# Full_set.net
KiCad netlist of a schematic drawn in EAGLE
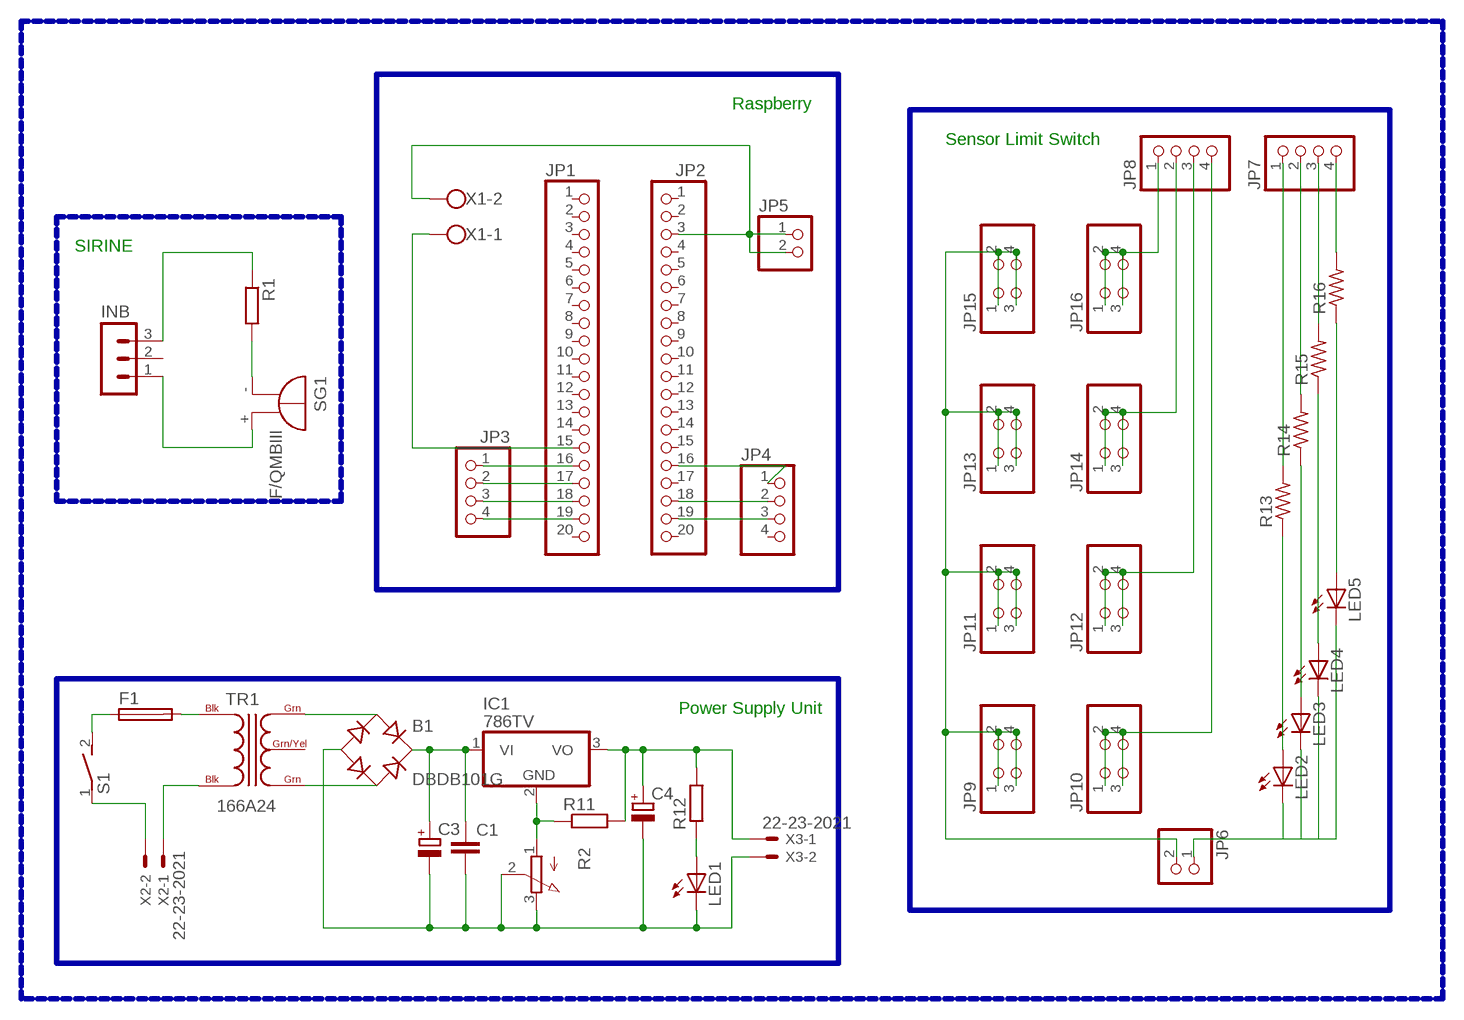
[diagram p0: schematic, sheet 1]

(export (version "E")
  (design (tool "Eeschema 10.0.6"))
  (components
    (comp (ref "B1")
      (value "DBDB101G")
      (footprint "eagle-import:DB")
      (libsource (lib "eagle-import") (part "DB?GDB101"))
    )
    (comp (ref "C1")
      (value "C-EU075-032X103")
      (footprint "eagle-import:C075-032X103")
      (libsource (lib "eagle-import") (part "C-EU075-032X103"))
    )
    (comp (ref "C3")
      (value "CPOL-EUE5-8.5")
      (footprint "eagle-import:E5-8,5")
      (libsource (lib "eagle-import") (part "CPOL-EUE5-8.5"))
    )
    (comp (ref "C4")
      (value "CPOL-EUE5-6")
      (footprint "eagle-import:E5-6")
      (libsource (lib "eagle-import") (part "CPOL-EUE5-6"))
    )
    (comp (ref "F1")
      (value "19560")
      (footprint "eagle-import:19560")
      (fields (field (name "MPN") "56000001009"))
      (libsource (lib "eagle-import") (part "19560"))
    )
    (comp (ref "IC1")
      (value "786TV")
      (footprint "eagle-import:TO220V")
      (libsource (lib "eagle-import") (part "78TV6"))
    )
    (comp (ref "INB")
      (value "MA03-1")
      (footprint "eagle-import:MA03-1")
      (libsource (lib "eagle-import") (part "MA03-1"))
    )
    (comp (ref "JP1")
      (value "PINHD-1X20")
      (footprint "eagle-import:1X20")
      (libsource (lib "eagle-import") (part "PINHD-1X20"))
    )
    (comp (ref "JP2")
      (value "PINHD-1X20")
      (footprint "eagle-import:1X20")
      (libsource (lib "eagle-import") (part "PINHD-1X20"))
    )
    (comp (ref "JP3")
      (value "PINHD-1X4")
      (footprint "eagle-import:1X04")
      (libsource (lib "eagle-import") (part "PINHD-1X4"))
    )
    (comp (ref "JP4")
      (value "PINHD-1X4")
      (footprint "eagle-import:1X04")
      (libsource (lib "eagle-import") (part "PINHD-1X4"))
    )
    (comp (ref "JP5")
      (value "PINHD-1X2")
      (footprint "eagle-import:1X02")
      (libsource (lib "eagle-import") (part "PINHD-1X2"))
    )
    (comp (ref "JP6")
      (value "PINHD-1X2")
      (footprint "eagle-import:1X02")
      (libsource (lib "eagle-import") (part "PINHD-1X2"))
    )
    (comp (ref "JP7")
      (value "PINHD-1X4")
      (footprint "eagle-import:1X04")
      (libsource (lib "eagle-import") (part "PINHD-1X4"))
    )
    (comp (ref "JP8")
      (value "PINHD-1X4")
      (footprint "eagle-import:1X04")
      (libsource (lib "eagle-import") (part "PINHD-1X4"))
    )
    (comp (ref "JP9")
      (value "PINHD-2X2")
      (footprint "eagle-import:2X02")
      (libsource (lib "eagle-import") (part "PINHD-2X2"))
    )
    (comp (ref "JP10")
      (value "PINHD-2X2")
      (footprint "eagle-import:2X02")
      (libsource (lib "eagle-import") (part "PINHD-2X2"))
    )
    (comp (ref "JP11")
      (value "PINHD-2X2")
      (footprint "eagle-import:2X02")
      (libsource (lib "eagle-import") (part "PINHD-2X2"))
    )
    (comp (ref "JP12")
      (value "PINHD-2X2")
      (footprint "eagle-import:2X02")
      (libsource (lib "eagle-import") (part "PINHD-2X2"))
    )
    (comp (ref "JP13")
      (value "PINHD-2X2")
      (footprint "eagle-import:2X02")
      (libsource (lib "eagle-import") (part "PINHD-2X2"))
    )
    (comp (ref "JP14")
      (value "PINHD-2X2")
      (footprint "eagle-import:2X02")
      (libsource (lib "eagle-import") (part "PINHD-2X2"))
    )
    (comp (ref "JP15")
      (value "PINHD-2X2")
      (footprint "eagle-import:2X02")
      (libsource (lib "eagle-import") (part "PINHD-2X2"))
    )
    (comp (ref "JP16")
      (value "PINHD-2X2")
      (footprint "eagle-import:2X02")
      (libsource (lib "eagle-import") (part "PINHD-2X2"))
    )
    (comp (ref "LED1")
      (value "LEDB152")
      (footprint "eagle-import:Q62902-B152")
      (libsource (lib "eagle-import") (part "LEDB152"))
    )
    (comp (ref "LED2")
      (value "LED3MM")
      (footprint "eagle-import:LED3MM")
      (libsource (lib "eagle-import") (part "LED3MM"))
    )
    (comp (ref "LED3")
      (value "LED3MM")
      (footprint "eagle-import:LED3MM")
      (libsource (lib "eagle-import") (part "LED3MM"))
    )
    (comp (ref "LED4")
      (value "LED3MM")
      (footprint "eagle-import:LED3MM")
      (libsource (lib "eagle-import") (part "LED3MM"))
    )
    (comp (ref "LED5")
      (value "LED3MM")
      (footprint "eagle-import:LED3MM")
      (libsource (lib "eagle-import") (part "LED3MM"))
    )
    (comp (ref "R1")
      (value "R-EU_0204/5")
      (footprint "eagle-import:0204_5")
      (libsource (lib "eagle-import") (part "resistor_R-EU_0204/5"))
    )
    (comp (ref "R2")
      (value "3RP/1610N")
      (footprint "eagle-import:3RP_1610N")
      (libsource (lib "eagle-import") (part "3RP/1610N"))
    )
    (comp (ref "R11")
      (value "R-EU_0309/12")
      (footprint "eagle-import:0309_12")
      (libsource (lib "eagle-import") (part "R-EU_0309/12"))
    )
    (comp (ref "R12")
      (value "R-EU_0309/12")
      (footprint "eagle-import:0309_12")
      (libsource (lib "eagle-import") (part "R-EU_0309/12"))
    )
    (comp (ref "R13")
      (value "R-US_0207/10")
      (footprint "eagle-import:0207_10")
      (libsource (lib "eagle-import") (part "R-US_0207/10"))
    )
    (comp (ref "R14")
      (value "R-US_0207/10")
      (footprint "eagle-import:0207_10")
      (libsource (lib "eagle-import") (part "R-US_0207/10"))
    )
    (comp (ref "R15")
      (value "R-US_0207/10")
      (footprint "eagle-import:0207_10")
      (libsource (lib "eagle-import") (part "R-US_0207/10"))
    )
    (comp (ref "R16")
      (value "R-US_0207/10")
      (footprint "eagle-import:0207_10")
      (libsource (lib "eagle-import") (part "R-US_0207/10"))
    )
    (comp (ref "S1")
      (value "DS01E")
      (footprint "eagle-import:DS-01")
      (libsource (lib "eagle-import") (part "DS01E"))
    )
    (comp (ref "SG1")
      (value "F/QMBIII")
      (footprint "eagle-import:F_QMBIII")
      (libsource (lib "eagle-import") (part "F/QMBIII"))
    )
    (comp (ref "TR1")
      (value "166A24")
      (footprint "eagle-import:C2H")
      (libsource (lib "eagle-import") (part "166A24"))
    )
    (comp (ref "X1")
      (value "W237-102")
      (footprint "eagle-import:W237-102")
      (fields (field (name "MPN") "237-102"))
      (libsource (lib "eagle-import") (part "W237-102"))
    )
    (comp (ref "X2")
      (value "22-23-2021")
      (footprint "eagle-import:22-23-2021")
      (fields (field (name "MF") "MOLEX"))
      (libsource (lib "eagle-import") (part "22-23-2021"))
    )
    (comp (ref "X3")
      (value "22-23-2021")
      (footprint "eagle-import:22-23-2021")
      (fields (field (name "MF") "MOLEX"))
      (libsource (lib "eagle-import") (part "22-23-2021"))
    )
  )
  (nets
    (net (code "1") (name "Net-(B1-PadAC1)") (class "Default")
      (node (ref "B1") (pin "AC1") (pinfunction "AC1_AC1") (pintype "passive"))
      (node (ref "TR1") (pin "GRN@1") (pinfunction "GRN_GRN@1") (pintype "passive"))
    )
    (net (code "2") (name "Net-(B1-PadAC2)") (class "Default")
      (node (ref "B1") (pin "AC2") (pinfunction "AC2_AC2") (pintype "passive"))
      (node (ref "TR1") (pin "GRN@2") (pinfunction "GRN_GRN@2") (pintype "passive"))
    )
    (net (code "3") (name "Net-(F1-Pad1)") (class "Default")
      (node (ref "F1") (pin "1") (pinfunction "1_1") (pintype "passive"))
      (node (ref "S1") (pin "2") (pinfunction "2_2") (pintype "passive"))
    )
    (net (code "4") (name "Net-(F1-Pad2)") (class "Default")
      (node (ref "F1") (pin "2") (pinfunction "2_2") (pintype "passive"))
      (node (ref "TR1") (pin "BLK@1") (pinfunction "BLK_BLK@1") (pintype "passive"))
    )
    (net (code "5") (name "Net-(IC1-GND)") (class "Default")
      (node (ref "IC1") (pin "2") (pinfunction "GND_2") (pintype "passive"))
      (node (ref "R11") (pin "1") (pinfunction "1_1") (pintype "passive"))
      (node (ref "R2") (pin "1") (pinfunction "A_1") (pintype "passive"))
    )
    (net (code "6") (name "Net-(IC1-VI)") (class "Default")
      (node (ref "B1") (pin "+") (pinfunction "+_+") (pintype "passive"))
      (node (ref "C1") (pin "1") (pinfunction "1_1") (pintype "passive"))
      (node (ref "C3") (pin "+") (pinfunction "+_+") (pintype "passive"))
      (node (ref "IC1") (pin "1") (pinfunction "VI_1") (pintype "input"))
    )
    (net (code "7") (name "Net-(IC1-VO)") (class "Default")
      (node (ref "C4") (pin "+") (pinfunction "+_+") (pintype "passive"))
      (node (ref "IC1") (pin "3") (pinfunction "VO_3") (pintype "passive"))
      (node (ref "R11") (pin "2") (pinfunction "2_2") (pintype "passive"))
      (node (ref "R12") (pin "2") (pinfunction "2_2") (pintype "passive"))
      (node (ref "X3") (pin "1") (pinfunction "S_1") (pintype "passive"))
    )
    (net (code "8") (name "Net-(INB-Pad3)") (class "Default")
      (node (ref "INB") (pin "3") (pinfunction "3_3") (pintype "passive"))
      (node (ref "R1") (pin "1") (pinfunction "1_1") (pintype "passive"))
    )
    (net (code "9") (name "Net-(JP1-Pad16)") (class "Default")
      (node (ref "JP1") (pin "16") (pinfunction "16_16") (pintype "passive"))
      (node (ref "JP3") (pin "1") (pinfunction "1_1") (pintype "passive"))
    )
    (net (code "10") (name "Net-(JP1-Pad17)") (class "Default")
      (node (ref "JP1") (pin "17") (pinfunction "17_17") (pintype "passive"))
      (node (ref "JP3") (pin "2") (pinfunction "2_2") (pintype "passive"))
    )
    (net (code "11") (name "Net-(JP1-Pad18)") (class "Default")
      (node (ref "JP1") (pin "18") (pinfunction "18_18") (pintype "passive"))
      (node (ref "JP3") (pin "3") (pinfunction "3_3") (pintype "passive"))
    )
    (net (code "12") (name "Net-(JP1-Pad19)") (class "Default")
      (node (ref "JP1") (pin "19") (pinfunction "19_19") (pintype "passive"))
      (node (ref "JP3") (pin "4") (pinfunction "4_4") (pintype "passive"))
    )
    (net (code "13") (name "Net-(JP2-Pad16)") (class "Default")
      (node (ref "JP2") (pin "16") (pinfunction "16_16") (pintype "passive"))
      (node (ref "JP4") (pin "1") (pinfunction "1_1") (pintype "passive"))
    )
    (net (code "14") (name "Net-(JP2-Pad18)") (class "Default")
      (node (ref "JP2") (pin "18") (pinfunction "18_18") (pintype "passive"))
      (node (ref "JP4") (pin "2") (pinfunction "2_2") (pintype "passive"))
    )
    (net (code "15") (name "Net-(JP2-Pad19)") (class "Default")
      (node (ref "JP2") (pin "19") (pinfunction "19_19") (pintype "passive"))
      (node (ref "JP4") (pin "3") (pinfunction "3_3") (pintype "passive"))
    )
    (net (code "16") (name "Net-(JP7-Pad1)") (class "Default")
      (node (ref "JP7") (pin "1") (pinfunction "1_1") (pintype "passive"))
      (node (ref "R13") (pin "2") (pinfunction "2_2") (pintype "passive"))
    )
    (net (code "17") (name "Net-(JP7-Pad2)") (class "Default")
      (node (ref "JP7") (pin "2") (pinfunction "2_2") (pintype "passive"))
      (node (ref "R14") (pin "2") (pinfunction "2_2") (pintype "passive"))
    )
    (net (code "18") (name "Net-(JP7-Pad3)") (class "Default")
      (node (ref "JP7") (pin "3") (pinfunction "3_3") (pintype "passive"))
      (node (ref "R15") (pin "2") (pinfunction "2_2") (pintype "passive"))
    )
    (net (code "19") (name "Net-(JP7-Pad4)") (class "Default")
      (node (ref "JP7") (pin "4") (pinfunction "4_4") (pintype "passive"))
      (node (ref "R16") (pin "2") (pinfunction "2_2") (pintype "passive"))
    )
    (net (code "20") (name "Net-(JP10-Pad1)") (class "Default")
      (node (ref "JP10") (pin "1") (pinfunction "1_1") (pintype "passive"))
      (node (ref "JP10") (pin "2") (pinfunction "2_2") (pintype "passive"))
      (node (ref "JP10") (pin "3") (pinfunction "3_3") (pintype "passive"))
      (node (ref "JP10") (pin "4") (pinfunction "4_4") (pintype "passive"))
      (node (ref "JP8") (pin "4") (pinfunction "4_4") (pintype "passive"))
    )
    (net (code "21") (name "Net-(JP11-Pad1)") (class "Default")
      (node (ref "JP11") (pin "1") (pinfunction "1_1") (pintype "passive"))
      (node (ref "JP11") (pin "2") (pinfunction "2_2") (pintype "passive"))
      (node (ref "JP11") (pin "3") (pinfunction "3_3") (pintype "passive"))
      (node (ref "JP11") (pin "4") (pinfunction "4_4") (pintype "passive"))
      (node (ref "JP13") (pin "1") (pinfunction "1_1") (pintype "passive"))
      (node (ref "JP13") (pin "2") (pinfunction "2_2") (pintype "passive"))
      (node (ref "JP13") (pin "3") (pinfunction "3_3") (pintype "passive"))
      (node (ref "JP13") (pin "4") (pinfunction "4_4") (pintype "passive"))
      (node (ref "JP15") (pin "1") (pinfunction "1_1") (pintype "passive"))
      (node (ref "JP15") (pin "2") (pinfunction "2_2") (pintype "passive"))
      (node (ref "JP15") (pin "3") (pinfunction "3_3") (pintype "passive"))
      (node (ref "JP15") (pin "4") (pinfunction "4_4") (pintype "passive"))
      (node (ref "JP6") (pin "2") (pinfunction "2_2") (pintype "passive"))
      (node (ref "JP9") (pin "1") (pinfunction "1_1") (pintype "passive"))
      (node (ref "JP9") (pin "2") (pinfunction "2_2") (pintype "passive"))
      (node (ref "JP9") (pin "3") (pinfunction "3_3") (pintype "passive"))
      (node (ref "JP9") (pin "4") (pinfunction "4_4") (pintype "passive"))
    )
    (net (code "22") (name "Net-(JP12-Pad1)") (class "Default")
      (node (ref "JP12") (pin "1") (pinfunction "1_1") (pintype "passive"))
      (node (ref "JP12") (pin "2") (pinfunction "2_2") (pintype "passive"))
      (node (ref "JP12") (pin "3") (pinfunction "3_3") (pintype "passive"))
      (node (ref "JP12") (pin "4") (pinfunction "4_4") (pintype "passive"))
      (node (ref "JP8") (pin "3") (pinfunction "3_3") (pintype "passive"))
    )
    (net (code "23") (name "Net-(JP14-Pad1)") (class "Default")
      (node (ref "JP14") (pin "1") (pinfunction "1_1") (pintype "passive"))
      (node (ref "JP14") (pin "2") (pinfunction "2_2") (pintype "passive"))
      (node (ref "JP14") (pin "3") (pinfunction "3_3") (pintype "passive"))
      (node (ref "JP14") (pin "4") (pinfunction "4_4") (pintype "passive"))
      (node (ref "JP8") (pin "2") (pinfunction "2_2") (pintype "passive"))
    )
    (net (code "24") (name "Net-(JP16-Pad1)") (class "Default")
      (node (ref "JP16") (pin "1") (pinfunction "1_1") (pintype "passive"))
      (node (ref "JP16") (pin "2") (pinfunction "2_2") (pintype "passive"))
      (node (ref "JP16") (pin "3") (pinfunction "3_3") (pintype "passive"))
      (node (ref "JP16") (pin "4") (pinfunction "4_4") (pintype "passive"))
      (node (ref "JP8") (pin "1") (pinfunction "1_1") (pintype "passive"))
    )
    (net (code "25") (name "Net-(LED1-C)") (class "Default")
      (node (ref "B1") (pin "-") (pinfunction "-_-") (pintype "passive"))
      (node (ref "C1") (pin "2") (pinfunction "2_2") (pintype "passive"))
      (node (ref "C3") (pin "-") (pinfunction "-_-") (pintype "passive"))
      (node (ref "C4") (pin "-") (pinfunction "-_-") (pintype "passive"))
      (node (ref "LED1") (pin "K") (pinfunction "C_K") (pintype "passive"))
      (node (ref "R2") (pin "2") (pinfunction "S_2") (pintype "passive"))
      (node (ref "R2") (pin "3") (pinfunction "E_3") (pintype "passive"))
      (node (ref "X3") (pin "2") (pinfunction "S_2") (pintype "passive"))
    )
    (net (code "26") (name "Net-(LED1-PadA)") (class "Default")
      (node (ref "LED1") (pin "A") (pinfunction "A_A") (pintype "passive"))
      (node (ref "R12") (pin "1") (pinfunction "1_1") (pintype "passive"))
    )
    (net (code "27") (name "Net-(LED2-C)") (class "Default")
      (node (ref "JP6") (pin "1") (pinfunction "1_1") (pintype "passive"))
      (node (ref "LED2") (pin "K") (pinfunction "C_K") (pintype "passive"))
      (node (ref "LED3") (pin "K") (pinfunction "C_K") (pintype "passive"))
      (node (ref "LED4") (pin "K") (pinfunction "C_K") (pintype "passive"))
      (node (ref "LED5") (pin "K") (pinfunction "C_K") (pintype "passive"))
    )
    (net (code "28") (name "Net-(LED2-PadA)") (class "Default")
      (node (ref "LED2") (pin "A") (pinfunction "A_A") (pintype "passive"))
      (node (ref "R13") (pin "1") (pinfunction "1_1") (pintype "passive"))
    )
    (net (code "29") (name "Net-(LED3-PadA)") (class "Default")
      (node (ref "LED3") (pin "A") (pinfunction "A_A") (pintype "passive"))
      (node (ref "R14") (pin "1") (pinfunction "1_1") (pintype "passive"))
    )
    (net (code "30") (name "Net-(LED4-PadA)") (class "Default")
      (node (ref "LED4") (pin "A") (pinfunction "A_A") (pintype "passive"))
      (node (ref "R15") (pin "1") (pinfunction "1_1") (pintype "passive"))
    )
    (net (code "31") (name "Net-(LED5-PadA)") (class "Default")
      (node (ref "LED5") (pin "A") (pinfunction "A_A") (pintype "passive"))
      (node (ref "R16") (pin "1") (pinfunction "1_1") (pintype "passive"))
    )
    (net (code "32") (name "Net-(SG1-+)") (class "Default")
      (node (ref "R1") (pin "2") (pinfunction "2_2") (pintype "passive"))
      (node (ref "SG1") (pin "-") (pinfunction "+_-") (pintype "passive"))
    )
    (net (code "33") (name "Net-(SG1--)") (class "Default")
      (node (ref "INB") (pin "1") (pinfunction "1_1") (pintype "passive"))
      (node (ref "SG1") (pin "+") (pinfunction "-_+") (pintype "passive"))
    )
    (net (code "34") (name "Net-(X1A-KL)") (class "Default")
      (node (ref "JP1") (pin "15") (pinfunction "15_15") (pintype "passive"))
      (node (ref "X1") (pin "1") (pinfunction "KL_1") (pintype "passive"))
    )
    (net (code "35") (name "Net-(X1B-KL)") (class "Default")
      (node (ref "JP2") (pin "3") (pinfunction "3_3") (pintype "passive"))
      (node (ref "JP5") (pin "1") (pinfunction "1_1") (pintype "passive"))
      (node (ref "JP5") (pin "2") (pinfunction "2_2") (pintype "passive"))
      (node (ref "X1") (pin "2") (pinfunction "KL_2") (pintype "passive"))
    )
    (net (code "36") (name "Net-(X2A-S)") (class "Default")
      (node (ref "TR1") (pin "BLK@2") (pinfunction "BLK_BLK@2") (pintype "passive"))
      (node (ref "X2") (pin "1") (pinfunction "S_1") (pintype "passive"))
    )
    (net (code "37") (name "Net-(X2B-S)") (class "Default")
      (node (ref "S1") (pin "1") (pinfunction "1_1") (pintype "passive"))
      (node (ref "X2") (pin "2") (pinfunction "S_2") (pintype "passive"))
    )
    (net (code "38") (name "unconnected-(INB-Pad2)") (class "Default")
      (node (ref "INB") (pin "2") (pinfunction "2_2") (pintype "passive"))
    )
    (net (code "39") (name "unconnected-(JP1-Pad1)") (class "Default")
      (node (ref "JP1") (pin "1") (pinfunction "1_1") (pintype "passive"))
    )
    (net (code "40") (name "unconnected-(JP1-Pad2)") (class "Default")
      (node (ref "JP1") (pin "2") (pinfunction "2_2") (pintype "passive"))
    )
    (net (code "41") (name "unconnected-(JP1-Pad3)") (class "Default")
      (node (ref "JP1") (pin "3") (pinfunction "3_3") (pintype "passive"))
    )
    (net (code "42") (name "unconnected-(JP1-Pad4)") (class "Default")
      (node (ref "JP1") (pin "4") (pinfunction "4_4") (pintype "passive"))
    )
    (net (code "43") (name "unconnected-(JP1-Pad5)") (class "Default")
      (node (ref "JP1") (pin "5") (pinfunction "5_5") (pintype "passive"))
    )
    (net (code "44") (name "unconnected-(JP1-Pad6)") (class "Default")
      (node (ref "JP1") (pin "6") (pinfunction "6_6") (pintype "passive"))
    )
    (net (code "45") (name "unconnected-(JP1-Pad7)") (class "Default")
      (node (ref "JP1") (pin "7") (pinfunction "7_7") (pintype "passive"))
    )
    (net (code "46") (name "unconnected-(JP1-Pad8)") (class "Default")
      (node (ref "JP1") (pin "8") (pinfunction "8_8") (pintype "passive"))
    )
    (net (code "47") (name "unconnected-(JP1-Pad9)") (class "Default")
      (node (ref "JP1") (pin "9") (pinfunction "9_9") (pintype "passive"))
    )
    (net (code "48") (name "unconnected-(JP1-Pad10)") (class "Default")
      (node (ref "JP1") (pin "10") (pinfunction "10_10") (pintype "passive"))
    )
    (net (code "49") (name "unconnected-(JP1-Pad11)") (class "Default")
      (node (ref "JP1") (pin "11") (pinfunction "11_11") (pintype "passive"))
    )
    (net (code "50") (name "unconnected-(JP1-Pad12)") (class "Default")
      (node (ref "JP1") (pin "12") (pinfunction "12_12") (pintype "passive"))
    )
    (net (code "51") (name "unconnected-(JP1-Pad13)") (class "Default")
      (node (ref "JP1") (pin "13") (pinfunction "13_13") (pintype "passive"))
    )
    (net (code "52") (name "unconnected-(JP1-Pad14)") (class "Default")
      (node (ref "JP1") (pin "14") (pinfunction "14_14") (pintype "passive"))
    )
    (net (code "53") (name "unconnected-(JP1-Pad20)") (class "Default")
      (node (ref "JP1") (pin "20") (pinfunction "20_20") (pintype "passive"))
    )
    (net (code "54") (name "unconnected-(JP2-Pad1)") (class "Default")
      (node (ref "JP2") (pin "1") (pinfunction "1_1") (pintype "passive"))
    )
    (net (code "55") (name "unconnected-(JP2-Pad2)") (class "Default")
      (node (ref "JP2") (pin "2") (pinfunction "2_2") (pintype "passive"))
    )
    (net (code "56") (name "unconnected-(JP2-Pad4)") (class "Default")
      (node (ref "JP2") (pin "4") (pinfunction "4_4") (pintype "passive"))
    )
    (net (code "57") (name "unconnected-(JP2-Pad5)") (class "Default")
      (node (ref "JP2") (pin "5") (pinfunction "5_5") (pintype "passive"))
    )
    (net (code "58") (name "unconnected-(JP2-Pad6)") (class "Default")
      (node (ref "JP2") (pin "6") (pinfunction "6_6") (pintype "passive"))
    )
    (net (code "59") (name "unconnected-(JP2-Pad7)") (class "Default")
      (node (ref "JP2") (pin "7") (pinfunction "7_7") (pintype "passive"))
    )
    (net (code "60") (name "unconnected-(JP2-Pad8)") (class "Default")
      (node (ref "JP2") (pin "8") (pinfunction "8_8") (pintype "passive"))
    )
    (net (code "61") (name "unconnected-(JP2-Pad9)") (class "Default")
      (node (ref "JP2") (pin "9") (pinfunction "9_9") (pintype "passive"))
    )
    (net (code "62") (name "unconnected-(JP2-Pad10)") (class "Default")
      (node (ref "JP2") (pin "10") (pinfunction "10_10") (pintype "passive"))
    )
    (net (code "63") (name "unconnected-(JP2-Pad11)") (class "Default")
      (node (ref "JP2") (pin "11") (pinfunction "11_11") (pintype "passive"))
    )
    (net (code "64") (name "unconnected-(JP2-Pad12)") (class "Default")
      (node (ref "JP2") (pin "12") (pinfunction "12_12") (pintype "passive"))
    )
    (net (code "65") (name "unconnected-(JP2-Pad13)") (class "Default")
      (node (ref "JP2") (pin "13") (pinfunction "13_13") (pintype "passive"))
    )
    (net (code "66") (name "unconnected-(JP2-Pad14)") (class "Default")
      (node (ref "JP2") (pin "14") (pinfunction "14_14") (pintype "passive"))
    )
    (net (code "67") (name "unconnected-(JP2-Pad15)") (class "Default")
      (node (ref "JP2") (pin "15") (pinfunction "15_15") (pintype "passive"))
    )
    (net (code "68") (name "unconnected-(JP2-Pad17)") (class "Default")
      (node (ref "JP2") (pin "17") (pinfunction "17_17") (pintype "passive"))
    )
    (net (code "69") (name "unconnected-(JP2-Pad20)") (class "Default")
      (node (ref "JP2") (pin "20") (pinfunction "20_20") (pintype "passive"))
    )
    (net (code "70") (name "unconnected-(JP4-Pad4)") (class "Default")
      (node (ref "JP4") (pin "4") (pinfunction "4_4") (pintype "passive"))
    )
    (net (code "71") (name "unconnected-(TR1-PadGRN{slash}YEL)") (class "Default")
      (node (ref "TR1") (pin "GRN/YEL") (pinfunction "GRN/YEL_GRN/YEL") (pintype "passive"))
    )
  )
)
